# footwell_tiny.net
KiCad netlist of a schematic drawn in EAGLE
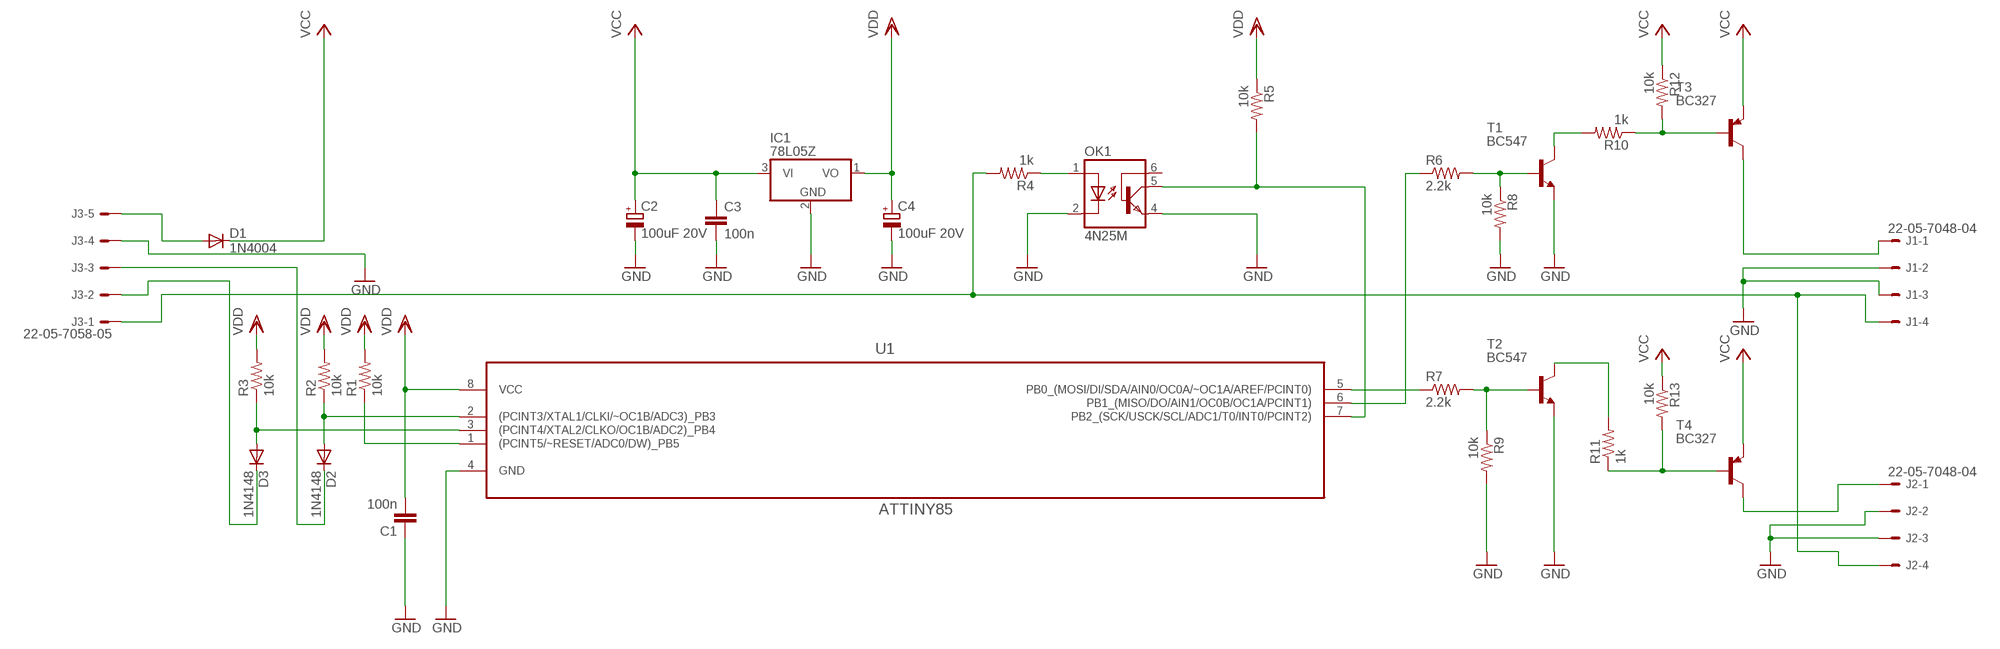
[diagram p0: schematic, sheet 1]

(export (version "E")
  (design (tool "Eeschema 10.0.6"))
  (components
    (comp (ref "C1")
      (value "100n")
      (footprint "eagle-import:C025-025X050")
      (libsource (lib "eagle-import") (part "C-EU025-025X050"))
    )
    (comp (ref "C2")
      (value "100uF 20V")
      (footprint "eagle-import:E3,5-8")
      (libsource (lib "eagle-import") (part "CPOL-EUE3.5-8"))
    )
    (comp (ref "C3")
      (value "100n")
      (footprint "eagle-import:C025-025X050")
      (libsource (lib "eagle-import") (part "C-EU025-025X050"))
    )
    (comp (ref "C4")
      (value "100uF 20V")
      (footprint "eagle-import:E3,5-8")
      (libsource (lib "eagle-import") (part "CPOL-EUE3.5-8"))
    )
    (comp (ref "D1")
      (value "1N4004")
      (footprint "eagle-import:DO41-10")
      (libsource (lib "eagle-import") (part "1N4004"))
    )
    (comp (ref "D2")
      (value "1N4148")
      (footprint "eagle-import:DO35-10")
      (libsource (lib "eagle-import") (part "1N4148"))
    )
    (comp (ref "D3")
      (value "1N4148")
      (footprint "eagle-import:DO35-10")
      (libsource (lib "eagle-import") (part "1N4148"))
    )
    (comp (ref "IC1")
      (value "78L05Z")
      (footprint "eagle-import:TO92")
      (libsource (lib "eagle-import") (part "78ZL05"))
    )
    (comp (ref "J1")
      (value "22-05-7048-04")
      (footprint "eagle-import:7395-04")
      (libsource (lib "eagle-import") (part "22-?-0405-7048"))
    )
    (comp (ref "J2")
      (value "22-05-7048-04")
      (footprint "eagle-import:7395-04")
      (libsource (lib "eagle-import") (part "22-?-0405-7048"))
    )
    (comp (ref "J3")
      (value "22-05-7058-05")
      (footprint "eagle-import:7395-05")
      (libsource (lib "eagle-import") (part "22-?-0505-7058"))
    )
    (comp (ref "OK1")
      (value "4N25M")
      (footprint "eagle-import:DIL06")
      (fields (field (name "MPN") "4N25-M"))
      (libsource (lib "eagle-import") (part "4N?M25"))
    )
    (comp (ref "R1")
      (value "10k")
      (footprint "eagle-import:0207_10")
      (libsource (lib "eagle-import") (part "R-US_0207/10"))
    )
    (comp (ref "R2")
      (value "10k")
      (footprint "eagle-import:0207_10")
      (libsource (lib "eagle-import") (part "R-US_0207/10"))
    )
    (comp (ref "R3")
      (value "10k")
      (footprint "eagle-import:0207_10")
      (libsource (lib "eagle-import") (part "R-US_0207/10"))
    )
    (comp (ref "R4")
      (value "1k")
      (footprint "eagle-import:0207_10")
      (libsource (lib "eagle-import") (part "R-US_0207/10"))
    )
    (comp (ref "R5")
      (value "10k")
      (footprint "eagle-import:0207_10")
      (libsource (lib "eagle-import") (part "R-US_0207/10"))
    )
    (comp (ref "R6")
      (value "2.2k")
      (footprint "eagle-import:0207_10")
      (libsource (lib "eagle-import") (part "R-US_0207/10"))
    )
    (comp (ref "R7")
      (value "2.2k")
      (footprint "eagle-import:0207_10")
      (libsource (lib "eagle-import") (part "R-US_0207/10"))
    )
    (comp (ref "R8")
      (value "10k")
      (footprint "eagle-import:0207_10")
      (libsource (lib "eagle-import") (part "R-US_0207/10"))
    )
    (comp (ref "R9")
      (value "10k")
      (footprint "eagle-import:0207_10")
      (libsource (lib "eagle-import") (part "R-US_0207/10"))
    )
    (comp (ref "R10")
      (value "1k")
      (footprint "eagle-import:0207_10")
      (libsource (lib "eagle-import") (part "R-US_0207/10"))
    )
    (comp (ref "R11")
      (value "1k")
      (footprint "eagle-import:0207_10")
      (libsource (lib "eagle-import") (part "R-US_0207/10"))
    )
    (comp (ref "R12")
      (value "10k")
      (footprint "eagle-import:0207_10")
      (libsource (lib "eagle-import") (part "R-US_0207/10"))
    )
    (comp (ref "R13")
      (value "10k")
      (footprint "eagle-import:0207_10")
      (libsource (lib "eagle-import") (part "R-US_0207/10"))
    )
    (comp (ref "T1")
      (value "BC547")
      (footprint "eagle-import:TO92-CBE")
      (libsource (lib "eagle-import") (part "-NPN-TO92-CBEBC547"))
    )
    (comp (ref "T2")
      (value "BC547")
      (footprint "eagle-import:TO92-CBE")
      (libsource (lib "eagle-import") (part "-NPN-TO92-CBEBC547"))
    )
    (comp (ref "T3")
      (value "BC327")
      (footprint "eagle-import:TO92-EBC")
      (libsource (lib "eagle-import") (part "BC327-25"))
    )
    (comp (ref "T4")
      (value "BC327")
      (footprint "eagle-import:TO92-EBC")
      (libsource (lib "eagle-import") (part "BC327-25"))
    )
    (comp (ref "U1")
      (value "ATTINY85")
      (footprint "eagle-import:DIP254P762X533-8")
      (fields (field (name "MPN") "ATTINY85-20PU"))
      (libsource (lib "eagle-import") (part "ATTINY85-20PU"))
    )
  )
  (nets
    (net (code "1") (name "GND") (class "Default")
      (node (ref "C1") (pin "1") (pinfunction "1_1") (pintype "passive"))
      (node (ref "C2") (pin "-") (pinfunction "-_-") (pintype "passive"))
      (node (ref "C3") (pin "2") (pinfunction "2_2") (pintype "passive"))
      (node (ref "C4") (pin "-") (pinfunction "-_-") (pintype "passive"))
      (node (ref "IC1") (pin "2") (pinfunction "GND_2") (pintype "passive"))
      (node (ref "J1") (pin "2") (pinfunction "S_2") (pintype "passive"))
      (node (ref "J1") (pin "3") (pinfunction "S_3") (pintype "passive"))
      (node (ref "J2") (pin "2") (pinfunction "S_2") (pintype "passive"))
      (node (ref "J2") (pin "3") (pinfunction "S_3") (pintype "passive"))
      (node (ref "J3") (pin "4") (pinfunction "S_4") (pintype "passive"))
      (node (ref "OK1") (pin "2") (pinfunction "C_2") (pintype "passive"))
      (node (ref "OK1") (pin "4") (pinfunction "EMI_4") (pintype "passive"))
      (node (ref "R8") (pin "2") (pinfunction "2_2") (pintype "passive"))
      (node (ref "R9") (pin "2") (pinfunction "2_2") (pintype "passive"))
      (node (ref "T1") (pin "E") (pinfunction "E_E") (pintype "passive"))
      (node (ref "T2") (pin "E") (pinfunction "E_E") (pintype "passive"))
      (node (ref "U1") (pin "4") (pinfunction "GND_4") (pintype "passive"))
    )
    (net (code "2") (name "Net-(J1A-S)") (class "Default")
      (node (ref "J1") (pin "1") (pinfunction "S_1") (pintype "passive"))
      (node (ref "T3") (pin "C") (pinfunction "C_C") (pintype "passive"))
    )
    (net (code "3") (name "Net-(J1D-S)") (class "Default")
      (node (ref "J1") (pin "4") (pinfunction "S_4") (pintype "passive"))
      (node (ref "J2") (pin "4") (pinfunction "S_4") (pintype "passive"))
      (node (ref "J3") (pin "1") (pinfunction "S_1") (pintype "passive"))
      (node (ref "R4") (pin "2") (pinfunction "2_2") (pintype "passive"))
    )
    (net (code "4") (name "Net-(J2A-S)") (class "Default")
      (node (ref "J2") (pin "1") (pinfunction "S_1") (pintype "passive"))
      (node (ref "T4") (pin "C") (pinfunction "C_C") (pintype "passive"))
    )
    (net (code "5") (name "Net-(J3B-S)") (class "Default")
      (node (ref "D3") (pin "C") (pinfunction "C_C") (pintype "passive"))
      (node (ref "J3") (pin "2") (pinfunction "S_2") (pintype "passive"))
    )
    (net (code "6") (name "Net-(J3C-S)") (class "Default")
      (node (ref "D2") (pin "C") (pinfunction "C_C") (pintype "passive"))
      (node (ref "J3") (pin "3") (pinfunction "S_3") (pintype "passive"))
    )
    (net (code "7") (name "Net-(J3E-S)") (class "Default")
      (node (ref "D1") (pin "A") (pinfunction "A_A") (pintype "passive"))
      (node (ref "J3") (pin "5") (pinfunction "S_5") (pintype "passive"))
    )
    (net (code "8") (name "Net-(OK1-A)") (class "Default")
      (node (ref "OK1") (pin "1") (pinfunction "A_1") (pintype "passive"))
      (node (ref "R4") (pin "1") (pinfunction "1_1") (pintype "passive"))
    )
    (net (code "9") (name "Net-(OK1-COL)") (class "Default")
      (node (ref "OK1") (pin "5") (pinfunction "COL_5") (pintype "passive"))
      (node (ref "R5") (pin "2") (pinfunction "2_2") (pintype "passive"))
      (node (ref "U1") (pin "7") (pinfunction "PB2_(SCK/USCK/SCL/ADC1/T0/INT0/PCINT2)_7") (pintype "bidirectional"))
    )
    (net (code "10") (name "Net-(R6-Pad2)") (class "Default")
      (node (ref "R6") (pin "2") (pinfunction "2_2") (pintype "passive"))
      (node (ref "R8") (pin "1") (pinfunction "1_1") (pintype "passive"))
      (node (ref "T1") (pin "B") (pinfunction "B_B") (pintype "passive"))
    )
    (net (code "11") (name "Net-(R7-Pad2)") (class "Default")
      (node (ref "R7") (pin "2") (pinfunction "2_2") (pintype "passive"))
      (node (ref "R9") (pin "1") (pinfunction "1_1") (pintype "passive"))
      (node (ref "T2") (pin "B") (pinfunction "B_B") (pintype "passive"))
    )
    (net (code "12") (name "Net-(R10-Pad1)") (class "Default")
      (node (ref "R10") (pin "1") (pinfunction "1_1") (pintype "passive"))
      (node (ref "R12") (pin "2") (pinfunction "2_2") (pintype "passive"))
      (node (ref "T3") (pin "B") (pinfunction "B_B") (pintype "passive"))
    )
    (net (code "13") (name "Net-(R10-Pad2)") (class "Default")
      (node (ref "R10") (pin "2") (pinfunction "2_2") (pintype "passive"))
      (node (ref "T1") (pin "C") (pinfunction "C_C") (pintype "passive"))
    )
    (net (code "14") (name "Net-(R11-Pad1)") (class "Default")
      (node (ref "R11") (pin "1") (pinfunction "1_1") (pintype "passive"))
      (node (ref "R13") (pin "2") (pinfunction "2_2") (pintype "passive"))
      (node (ref "T4") (pin "B") (pinfunction "B_B") (pintype "passive"))
    )
    (net (code "15") (name "Net-(R11-Pad2)") (class "Default")
      (node (ref "R11") (pin "2") (pinfunction "2_2") (pintype "passive"))
      (node (ref "T2") (pin "C") (pinfunction "C_C") (pintype "passive"))
    )
    (net (code "16") (name "Net-(U1-(PCINT3{slash}XTAL1{slash}CLKI{slash}~{OC1B{slash}ADC3})_PB3)") (class "Default")
      (node (ref "D2") (pin "A") (pinfunction "A_A") (pintype "passive"))
      (node (ref "R2") (pin "1") (pinfunction "1_1") (pintype "passive"))
      (node (ref "U1") (pin "2") (pinfunction "(PCINT3/XTAL1/CLKI/~{OC1B/ADC3})_PB3_2") (pintype "bidirectional"))
    )
    (net (code "17") (name "Net-(U1-(PCINT4{slash}XTAL2{slash}CLKO{slash}OC1B{slash}ADC2)_PB4)") (class "Default")
      (node (ref "D3") (pin "A") (pinfunction "A_A") (pintype "passive"))
      (node (ref "R3") (pin "1") (pinfunction "1_1") (pintype "passive"))
      (node (ref "U1") (pin "3") (pinfunction "(PCINT4/XTAL2/CLKO/OC1B/ADC2)_PB4_3") (pintype "bidirectional"))
    )
    (net (code "18") (name "Net-(U1-(PCINT5{slash}~{RESET{slash}ADC0{slash}DW})_PB5)") (class "Default")
      (node (ref "R1") (pin "1") (pinfunction "1_1") (pintype "passive"))
      (node (ref "U1") (pin "1") (pinfunction "(PCINT5/~{RESET/ADC0/DW})_PB5_1") (pintype "bidirectional"))
    )
    (net (code "19") (name "Net-(U1-PB0_(MOSI{slash}DI{slash}SDA{slash}AIN0{slash}OC0A{slash}~{OC1A{slash}AREF{slash}PCINT0}))") (class "Default")
      (node (ref "R7") (pin "1") (pinfunction "1_1") (pintype "passive"))
      (node (ref "U1") (pin "5") (pinfunction "PB0_(MOSI/DI/SDA/AIN0/OC0A/~{OC1A/AREF/PCINT0})_5") (pintype "bidirectional"))
    )
    (net (code "20") (name "Net-(U1-PB1_(MISO{slash}DO{slash}AIN1{slash}OC0B{slash}OC1A{slash}PCINT1))") (class "Default")
      (node (ref "R6") (pin "1") (pinfunction "1_1") (pintype "passive"))
      (node (ref "U1") (pin "6") (pinfunction "PB1_(MISO/DO/AIN1/OC0B/OC1A/PCINT1)_6") (pintype "bidirectional"))
    )
    (net (code "21") (name "VCC") (class "Default")
      (node (ref "C2") (pin "+") (pinfunction "+_+") (pintype "passive"))
      (node (ref "C3") (pin "1") (pinfunction "1_1") (pintype "passive"))
      (node (ref "D1") (pin "C") (pinfunction "C_C") (pintype "passive"))
      (node (ref "IC1") (pin "3") (pinfunction "VI_3") (pintype "input"))
      (node (ref "R12") (pin "1") (pinfunction "1_1") (pintype "passive"))
      (node (ref "R13") (pin "1") (pinfunction "1_1") (pintype "passive"))
      (node (ref "T3") (pin "E") (pinfunction "E_E") (pintype "passive"))
      (node (ref "T4") (pin "E") (pinfunction "E_E") (pintype "passive"))
    )
    (net (code "22") (name "VDD") (class "Default")
      (node (ref "C1") (pin "2") (pinfunction "2_2") (pintype "passive"))
      (node (ref "C4") (pin "+") (pinfunction "+_+") (pintype "passive"))
      (node (ref "IC1") (pin "1") (pinfunction "VO_1") (pintype "passive"))
      (node (ref "R1") (pin "2") (pinfunction "2_2") (pintype "passive"))
      (node (ref "R2") (pin "2") (pinfunction "2_2") (pintype "passive"))
      (node (ref "R3") (pin "2") (pinfunction "2_2") (pintype "passive"))
      (node (ref "R5") (pin "1") (pinfunction "1_1") (pintype "passive"))
      (node (ref "U1") (pin "8") (pinfunction "VCC_8") (pintype "power_in"))
    )
    (net (code "23") (name "unconnected-(OK1-BAS-Pad6)") (class "Default")
      (node (ref "OK1") (pin "6") (pinfunction "BAS_6") (pintype "passive"))
    )
  )
)
